# Shield_H-Bridge.net
KiCad netlist of a schematic drawn in EAGLE
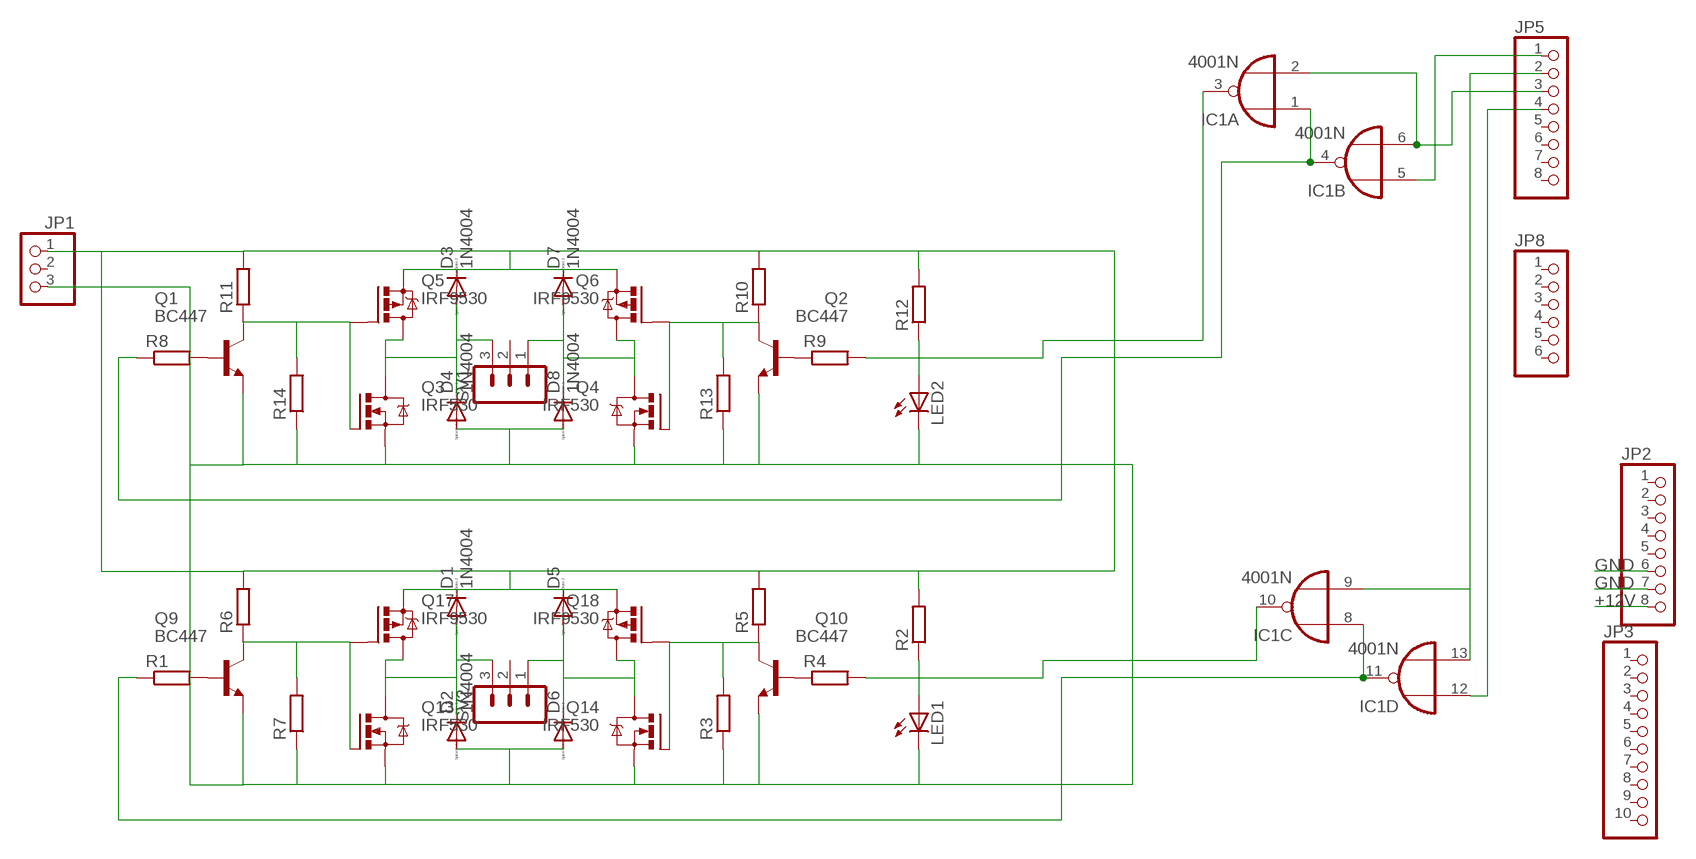
[diagram p0: schematic, sheet 1]

(export (version "E")
  (design (tool "Eeschema 10.0.6"))
  (components
    (comp (ref "D1")
      (value "1N4004")
      (footprint "eagle-import:DO41-10")
      (libsource (lib "eagle-import") (part "1N4004"))
    )
    (comp (ref "D2")
      (value "1N4004")
      (footprint "eagle-import:DO41-10")
      (libsource (lib "eagle-import") (part "1N4004"))
    )
    (comp (ref "D3")
      (value "1N4004")
      (footprint "eagle-import:DO41-10")
      (libsource (lib "eagle-import") (part "1N4004"))
    )
    (comp (ref "D4")
      (value "1N4004")
      (footprint "eagle-import:DO41-10")
      (libsource (lib "eagle-import") (part "1N4004"))
    )
    (comp (ref "D5")
      (value "1N4004")
      (footprint "eagle-import:DO41-10")
      (libsource (lib "eagle-import") (part "1N4004"))
    )
    (comp (ref "D6")
      (value "1N4004")
      (footprint "eagle-import:DO41-10")
      (libsource (lib "eagle-import") (part "1N4004"))
    )
    (comp (ref "D7")
      (value "1N4004")
      (footprint "eagle-import:DO41-10")
      (libsource (lib "eagle-import") (part "1N4004"))
    )
    (comp (ref "D8")
      (value "1N4004")
      (footprint "eagle-import:DO41-10")
      (libsource (lib "eagle-import") (part "1N4004"))
    )
    (comp (ref "IC1")
      (value "4001N")
      (footprint "eagle-import:DIL14")
      (libsource (lib "eagle-import") (part "4001N"))
    )
    (comp (ref "JP1")
      (value "PINHD-1X3")
      (footprint "eagle-import:1X03")
      (libsource (lib "eagle-import") (part "PINHD-1X3"))
    )
    (comp (ref "JP2")
      (value "PINHD-1X8")
      (footprint "eagle-import:1X08")
      (libsource (lib "eagle-import") (part "PINHD-1X8"))
    )
    (comp (ref "JP3")
      (value "PINHD-1X10")
      (footprint "eagle-import:1X10")
      (libsource (lib "eagle-import") (part "PINHD-1X10"))
    )
    (comp (ref "JP5")
      (value "PINHD-1X8")
      (footprint "eagle-import:1X08")
      (libsource (lib "eagle-import") (part "PINHD-1X8"))
    )
    (comp (ref "JP8")
      (value "PINHD-1X6")
      (footprint "eagle-import:1X06")
      (libsource (lib "eagle-import") (part "PINHD-1X6"))
    )
    (comp (ref "LED1")
      (value "LED3MM")
      (footprint "eagle-import:LED3MM")
      (libsource (lib "eagle-import") (part "LED3MM"))
    )
    (comp (ref "LED2")
      (value "LED3MM")
      (footprint "eagle-import:LED3MM")
      (libsource (lib "eagle-import") (part "LED3MM"))
    )
    (comp (ref "Q1")
      (value "BC447")
      (footprint "eagle-import:TO92-EBC")
      (libsource (lib "eagle-import") (part "BC447"))
    )
    (comp (ref "Q2")
      (value "BC447")
      (footprint "eagle-import:TO92-EBC")
      (libsource (lib "eagle-import") (part "BC447"))
    )
    (comp (ref "Q3")
      (value "IRF530")
      (footprint "eagle-import:TO220BV")
      (libsource (lib "eagle-import") (part "IRF530"))
    )
    (comp (ref "Q4")
      (value "IRF530")
      (footprint "eagle-import:TO220BV")
      (libsource (lib "eagle-import") (part "IRF530"))
    )
    (comp (ref "Q5")
      (value "IRF9530")
      (footprint "eagle-import:TO220BV")
      (libsource (lib "eagle-import") (part "IRF9530"))
    )
    (comp (ref "Q6")
      (value "IRF9530")
      (footprint "eagle-import:TO220BV")
      (libsource (lib "eagle-import") (part "IRF9530"))
    )
    (comp (ref "Q9")
      (value "BC447")
      (footprint "eagle-import:TO92-EBC")
      (libsource (lib "eagle-import") (part "BC447"))
    )
    (comp (ref "Q10")
      (value "BC447")
      (footprint "eagle-import:TO92-EBC")
      (libsource (lib "eagle-import") (part "BC447"))
    )
    (comp (ref "Q13")
      (value "IRF530")
      (footprint "eagle-import:TO220BV")
      (libsource (lib "eagle-import") (part "IRF530"))
    )
    (comp (ref "Q14")
      (value "IRF530")
      (footprint "eagle-import:TO220BV")
      (libsource (lib "eagle-import") (part "IRF530"))
    )
    (comp (ref "Q17")
      (value "IRF9530")
      (footprint "eagle-import:TO220BV")
      (libsource (lib "eagle-import") (part "IRF9530"))
    )
    (comp (ref "Q18")
      (value "IRF9530")
      (footprint "eagle-import:TO220BV")
      (libsource (lib "eagle-import") (part "IRF9530"))
    )
    (comp (ref "R1")
      (value "R-EU_0207/10")
      (footprint "eagle-import:0207_10")
      (libsource (lib "eagle-import") (part "R-EU_0207/10"))
    )
    (comp (ref "R2")
      (value "R-EU_0204/5")
      (footprint "eagle-import:0204_5")
      (libsource (lib "eagle-import") (part "R-EU_0204/5"))
    )
    (comp (ref "R3")
      (value "R-EU_0204/7")
      (footprint "eagle-import:0204_7")
      (libsource (lib "eagle-import") (part "R-EU_0204/7"))
    )
    (comp (ref "R4")
      (value "R-EU_0207/10")
      (footprint "eagle-import:0207_10")
      (libsource (lib "eagle-import") (part "R-EU_0207/10"))
    )
    (comp (ref "R5")
      (value "R-EU_0207/10")
      (footprint "eagle-import:0207_10")
      (libsource (lib "eagle-import") (part "R-EU_0207/10"))
    )
    (comp (ref "R6")
      (value "R-EU_0207/10")
      (footprint "eagle-import:0207_10")
      (libsource (lib "eagle-import") (part "R-EU_0207/10"))
    )
    (comp (ref "R7")
      (value "R-EU_0204/7")
      (footprint "eagle-import:0204_7")
      (libsource (lib "eagle-import") (part "R-EU_0204/7"))
    )
    (comp (ref "R8")
      (value "R-EU_0207/10")
      (footprint "eagle-import:0207_10")
      (libsource (lib "eagle-import") (part "R-EU_0207/10"))
    )
    (comp (ref "R9")
      (value "R-EU_0207/10")
      (footprint "eagle-import:0207_10")
      (libsource (lib "eagle-import") (part "R-EU_0207/10"))
    )
    (comp (ref "R10")
      (value "R-EU_0207/10")
      (footprint "eagle-import:0207_10")
      (libsource (lib "eagle-import") (part "R-EU_0207/10"))
    )
    (comp (ref "R11")
      (value "R-EU_0207/10")
      (footprint "eagle-import:0207_10")
      (libsource (lib "eagle-import") (part "R-EU_0207/10"))
    )
    (comp (ref "R12")
      (value "R-EU_0204/5")
      (footprint "eagle-import:0204_5")
      (libsource (lib "eagle-import") (part "R-EU_0204/5"))
    )
    (comp (ref "R13")
      (value "R-EU_0204/7")
      (footprint "eagle-import:0204_7")
      (libsource (lib "eagle-import") (part "R-EU_0204/7"))
    )
    (comp (ref "R14")
      (value "R-EU_0204/7")
      (footprint "eagle-import:0204_7")
      (libsource (lib "eagle-import") (part "R-EU_0204/7"))
    )
    (comp (ref "SV1")
      (value "MA03-1")
      (footprint "eagle-import:MA03-1")
      (libsource (lib "eagle-import") (part "MA03-1"))
    )
    (comp (ref "SV2")
      (value "MA03-1")
      (footprint "eagle-import:MA03-1")
      (libsource (lib "eagle-import") (part "MA03-1"))
    )
  )
  (nets
    (net (code "1") (name "/+12V") (class "Default")
      (node (ref "D1") (pin "C") (pinfunction "C_C") (pintype "passive"))
      (node (ref "D3") (pin "C") (pinfunction "C_C") (pintype "passive"))
      (node (ref "D5") (pin "C") (pinfunction "C_C") (pintype "passive"))
      (node (ref "D7") (pin "C") (pinfunction "C_C") (pintype "passive"))
      (node (ref "JP1") (pin "1") (pinfunction "1_1") (pintype "passive"))
      (node (ref "JP2") (pin "8") (pinfunction "8_8") (pintype "passive"))
      (node (ref "Q17") (pin "S") (pinfunction "S_S") (pintype "passive"))
      (node (ref "Q18") (pin "S") (pinfunction "S_S") (pintype "passive"))
      (node (ref "Q5") (pin "S") (pinfunction "S_S") (pintype "passive"))
      (node (ref "Q6") (pin "S") (pinfunction "S_S") (pintype "passive"))
      (node (ref "R10") (pin "2") (pinfunction "2_2") (pintype "passive"))
      (node (ref "R11") (pin "2") (pinfunction "2_2") (pintype "passive"))
      (node (ref "R12") (pin "2") (pinfunction "2_2") (pintype "passive"))
      (node (ref "R2") (pin "2") (pinfunction "2_2") (pintype "passive"))
      (node (ref "R5") (pin "2") (pinfunction "2_2") (pintype "passive"))
      (node (ref "R6") (pin "2") (pinfunction "2_2") (pintype "passive"))
    )
    (net (code "2") (name "/GND") (class "Default")
      (node (ref "D2") (pin "A") (pinfunction "A_A") (pintype "passive"))
      (node (ref "D4") (pin "A") (pinfunction "A_A") (pintype "passive"))
      (node (ref "D6") (pin "A") (pinfunction "A_A") (pintype "passive"))
      (node (ref "D8") (pin "A") (pinfunction "A_A") (pintype "passive"))
      (node (ref "JP1") (pin "3") (pinfunction "3_3") (pintype "passive"))
      (node (ref "JP2") (pin "6") (pinfunction "6_6") (pintype "passive"))
      (node (ref "JP2") (pin "7") (pinfunction "7_7") (pintype "passive"))
      (node (ref "LED1") (pin "K") (pinfunction "C_K") (pintype "passive"))
      (node (ref "LED2") (pin "K") (pinfunction "C_K") (pintype "passive"))
      (node (ref "Q1") (pin "E") (pinfunction "E_E") (pintype "passive"))
      (node (ref "Q10") (pin "E") (pinfunction "E_E") (pintype "passive"))
      (node (ref "Q13") (pin "S") (pinfunction "S_S") (pintype "passive"))
      (node (ref "Q14") (pin "S") (pinfunction "S_S") (pintype "passive"))
      (node (ref "Q2") (pin "E") (pinfunction "E_E") (pintype "passive"))
      (node (ref "Q3") (pin "S") (pinfunction "S_S") (pintype "passive"))
      (node (ref "Q4") (pin "S") (pinfunction "S_S") (pintype "passive"))
      (node (ref "Q9") (pin "E") (pinfunction "E_E") (pintype "passive"))
      (node (ref "R13") (pin "1") (pinfunction "1_1") (pintype "passive"))
      (node (ref "R14") (pin "1") (pinfunction "1_1") (pintype "passive"))
      (node (ref "R3") (pin "1") (pinfunction "1_1") (pintype "passive"))
      (node (ref "R7") (pin "1") (pinfunction "1_1") (pintype "passive"))
    )
    (net (code "3") (name "Net-(D1-PadA)") (class "Default")
      (node (ref "D1") (pin "A") (pinfunction "A_A") (pintype "passive"))
      (node (ref "D2") (pin "C") (pinfunction "C_C") (pintype "passive"))
      (node (ref "Q13") (pin "D") (pinfunction "D_D") (pintype "passive"))
      (node (ref "Q17") (pin "D") (pinfunction "D_D") (pintype "passive"))
      (node (ref "SV2") (pin "3") (pinfunction "3_3") (pintype "passive"))
    )
    (net (code "4") (name "Net-(D3-PadA)") (class "Default")
      (node (ref "D3") (pin "A") (pinfunction "A_A") (pintype "passive"))
      (node (ref "D4") (pin "C") (pinfunction "C_C") (pintype "passive"))
      (node (ref "Q3") (pin "D") (pinfunction "D_D") (pintype "passive"))
      (node (ref "Q5") (pin "D") (pinfunction "D_D") (pintype "passive"))
      (node (ref "SV1") (pin "3") (pinfunction "3_3") (pintype "passive"))
    )
    (net (code "5") (name "Net-(D5-PadA)") (class "Default")
      (node (ref "D5") (pin "A") (pinfunction "A_A") (pintype "passive"))
      (node (ref "D6") (pin "C") (pinfunction "C_C") (pintype "passive"))
      (node (ref "Q14") (pin "D") (pinfunction "D_D") (pintype "passive"))
      (node (ref "Q18") (pin "D") (pinfunction "D_D") (pintype "passive"))
      (node (ref "SV2") (pin "1") (pinfunction "1_1") (pintype "passive"))
    )
    (net (code "6") (name "Net-(D7-PadA)") (class "Default")
      (node (ref "D7") (pin "A") (pinfunction "A_A") (pintype "passive"))
      (node (ref "D8") (pin "C") (pinfunction "C_C") (pintype "passive"))
      (node (ref "Q4") (pin "D") (pinfunction "D_D") (pintype "passive"))
      (node (ref "Q6") (pin "D") (pinfunction "D_D") (pintype "passive"))
      (node (ref "SV1") (pin "1") (pinfunction "1_1") (pintype "passive"))
    )
    (net (code "7") (name "Net-(IC1A-I0)") (class "Default")
      (node (ref "IC1") (pin "1") (pinfunction "I0_1") (pintype "input"))
      (node (ref "IC1") (pin "4") (pinfunction "O_4") (pintype "output"))
      (node (ref "R8") (pin "1") (pinfunction "1_1") (pintype "passive"))
    )
    (net (code "8") (name "Net-(IC1A-I1)") (class "Default")
      (node (ref "IC1") (pin "2") (pinfunction "I1_2") (pintype "input"))
      (node (ref "IC1") (pin "6") (pinfunction "I1_6") (pintype "input"))
      (node (ref "JP5") (pin "3") (pinfunction "3_3") (pintype "passive"))
    )
    (net (code "9") (name "Net-(IC1A-O)") (class "Default")
      (node (ref "IC1") (pin "3") (pinfunction "O_3") (pintype "output"))
      (node (ref "R9") (pin "2") (pinfunction "2_2") (pintype "passive"))
    )
    (net (code "10") (name "Net-(IC1B-I0)") (class "Default")
      (node (ref "IC1") (pin "5") (pinfunction "I0_5") (pintype "input"))
      (node (ref "JP5") (pin "1") (pinfunction "1_1") (pintype "passive"))
    )
    (net (code "11") (name "Net-(IC1C-I0)") (class "Default")
      (node (ref "IC1") (pin "11") (pinfunction "O_11") (pintype "output"))
      (node (ref "IC1") (pin "8") (pinfunction "I0_8") (pintype "input"))
      (node (ref "R1") (pin "1") (pinfunction "1_1") (pintype "passive"))
    )
    (net (code "12") (name "Net-(IC1C-I1)") (class "Default")
      (node (ref "IC1") (pin "13") (pinfunction "I1_13") (pintype "input"))
      (node (ref "IC1") (pin "9") (pinfunction "I1_9") (pintype "input"))
      (node (ref "JP5") (pin "2") (pinfunction "2_2") (pintype "passive"))
    )
    (net (code "13") (name "Net-(IC1C-O)") (class "Default")
      (node (ref "IC1") (pin "10") (pinfunction "O_10") (pintype "output"))
      (node (ref "R4") (pin "2") (pinfunction "2_2") (pintype "passive"))
    )
    (net (code "14") (name "Net-(IC1D-I0)") (class "Default")
      (node (ref "IC1") (pin "12") (pinfunction "I0_12") (pintype "input"))
      (node (ref "JP5") (pin "4") (pinfunction "4_4") (pintype "passive"))
    )
    (net (code "15") (name "Net-(LED1-PadA)") (class "Default")
      (node (ref "LED1") (pin "A") (pinfunction "A_A") (pintype "passive"))
      (node (ref "R2") (pin "1") (pinfunction "1_1") (pintype "passive"))
    )
    (net (code "16") (name "Net-(LED2-PadA)") (class "Default")
      (node (ref "LED2") (pin "A") (pinfunction "A_A") (pintype "passive"))
      (node (ref "R12") (pin "1") (pinfunction "1_1") (pintype "passive"))
    )
    (net (code "17") (name "Net-(Q1-PadB)") (class "Default")
      (node (ref "Q1") (pin "B") (pinfunction "B_B") (pintype "passive"))
      (node (ref "R8") (pin "2") (pinfunction "2_2") (pintype "passive"))
    )
    (net (code "18") (name "Net-(Q1-PadC)") (class "Default")
      (node (ref "Q1") (pin "C") (pinfunction "C_C") (pintype "passive"))
      (node (ref "Q3") (pin "G") (pinfunction "G_G") (pintype "passive"))
      (node (ref "Q5") (pin "G") (pinfunction "G_G") (pintype "passive"))
      (node (ref "R11") (pin "1") (pinfunction "1_1") (pintype "passive"))
      (node (ref "R14") (pin "2") (pinfunction "2_2") (pintype "passive"))
    )
    (net (code "19") (name "Net-(Q2-PadB)") (class "Default")
      (node (ref "Q2") (pin "B") (pinfunction "B_B") (pintype "passive"))
      (node (ref "R9") (pin "1") (pinfunction "1_1") (pintype "passive"))
    )
    (net (code "20") (name "Net-(Q2-PadC)") (class "Default")
      (node (ref "Q2") (pin "C") (pinfunction "C_C") (pintype "passive"))
      (node (ref "Q4") (pin "G") (pinfunction "G_G") (pintype "passive"))
      (node (ref "Q6") (pin "G") (pinfunction "G_G") (pintype "passive"))
      (node (ref "R10") (pin "1") (pinfunction "1_1") (pintype "passive"))
      (node (ref "R13") (pin "2") (pinfunction "2_2") (pintype "passive"))
    )
    (net (code "21") (name "Net-(Q9-PadB)") (class "Default")
      (node (ref "Q9") (pin "B") (pinfunction "B_B") (pintype "passive"))
      (node (ref "R1") (pin "2") (pinfunction "2_2") (pintype "passive"))
    )
    (net (code "22") (name "Net-(Q10-PadB)") (class "Default")
      (node (ref "Q10") (pin "B") (pinfunction "B_B") (pintype "passive"))
      (node (ref "R4") (pin "1") (pinfunction "1_1") (pintype "passive"))
    )
    (net (code "23") (name "Net-(Q10-PadC)") (class "Default")
      (node (ref "Q10") (pin "C") (pinfunction "C_C") (pintype "passive"))
      (node (ref "Q14") (pin "G") (pinfunction "G_G") (pintype "passive"))
      (node (ref "Q18") (pin "G") (pinfunction "G_G") (pintype "passive"))
      (node (ref "R3") (pin "2") (pinfunction "2_2") (pintype "passive"))
      (node (ref "R5") (pin "1") (pinfunction "1_1") (pintype "passive"))
    )
    (net (code "24") (name "Net-(Q13-PadG)") (class "Default")
      (node (ref "Q13") (pin "G") (pinfunction "G_G") (pintype "passive"))
      (node (ref "Q17") (pin "G") (pinfunction "G_G") (pintype "passive"))
      (node (ref "Q9") (pin "C") (pinfunction "C_C") (pintype "passive"))
      (node (ref "R6") (pin "1") (pinfunction "1_1") (pintype "passive"))
      (node (ref "R7") (pin "2") (pinfunction "2_2") (pintype "passive"))
    )
    (net (code "25") (name "unconnected-(JP1-Pad2)") (class "Default")
      (node (ref "JP1") (pin "2") (pinfunction "2_2") (pintype "passive"))
    )
    (net (code "26") (name "unconnected-(JP2-Pad1)") (class "Default")
      (node (ref "JP2") (pin "1") (pinfunction "1_1") (pintype "passive"))
    )
    (net (code "27") (name "unconnected-(JP2-Pad2)") (class "Default")
      (node (ref "JP2") (pin "2") (pinfunction "2_2") (pintype "passive"))
    )
    (net (code "28") (name "unconnected-(JP2-Pad3)") (class "Default")
      (node (ref "JP2") (pin "3") (pinfunction "3_3") (pintype "passive"))
    )
    (net (code "29") (name "unconnected-(JP2-Pad4)") (class "Default")
      (node (ref "JP2") (pin "4") (pinfunction "4_4") (pintype "passive"))
    )
    (net (code "30") (name "unconnected-(JP2-Pad5)") (class "Default")
      (node (ref "JP2") (pin "5") (pinfunction "5_5") (pintype "passive"))
    )
    (net (code "31") (name "unconnected-(JP3-Pad1)") (class "Default")
      (node (ref "JP3") (pin "1") (pinfunction "1_1") (pintype "passive"))
    )
    (net (code "32") (name "unconnected-(JP3-Pad2)") (class "Default")
      (node (ref "JP3") (pin "2") (pinfunction "2_2") (pintype "passive"))
    )
    (net (code "33") (name "unconnected-(JP3-Pad3)") (class "Default")
      (node (ref "JP3") (pin "3") (pinfunction "3_3") (pintype "passive"))
    )
    (net (code "34") (name "unconnected-(JP3-Pad4)") (class "Default")
      (node (ref "JP3") (pin "4") (pinfunction "4_4") (pintype "passive"))
    )
    (net (code "35") (name "unconnected-(JP3-Pad5)") (class "Default")
      (node (ref "JP3") (pin "5") (pinfunction "5_5") (pintype "passive"))
    )
    (net (code "36") (name "unconnected-(JP3-Pad6)") (class "Default")
      (node (ref "JP3") (pin "6") (pinfunction "6_6") (pintype "passive"))
    )
    (net (code "37") (name "unconnected-(JP3-Pad7)") (class "Default")
      (node (ref "JP3") (pin "7") (pinfunction "7_7") (pintype "passive"))
    )
    (net (code "38") (name "unconnected-(JP3-Pad8)") (class "Default")
      (node (ref "JP3") (pin "8") (pinfunction "8_8") (pintype "passive"))
    )
    (net (code "39") (name "unconnected-(JP3-Pad9)") (class "Default")
      (node (ref "JP3") (pin "9") (pinfunction "9_9") (pintype "passive"))
    )
    (net (code "40") (name "unconnected-(JP3-Pad10)") (class "Default")
      (node (ref "JP3") (pin "10") (pinfunction "10_10") (pintype "passive"))
    )
    (net (code "41") (name "unconnected-(JP5-Pad5)") (class "Default")
      (node (ref "JP5") (pin "5") (pinfunction "5_5") (pintype "passive"))
    )
    (net (code "42") (name "unconnected-(JP5-Pad6)") (class "Default")
      (node (ref "JP5") (pin "6") (pinfunction "6_6") (pintype "passive"))
    )
    (net (code "43") (name "unconnected-(JP5-Pad7)") (class "Default")
      (node (ref "JP5") (pin "7") (pinfunction "7_7") (pintype "passive"))
    )
    (net (code "44") (name "unconnected-(JP5-Pad8)") (class "Default")
      (node (ref "JP5") (pin "8") (pinfunction "8_8") (pintype "passive"))
    )
    (net (code "45") (name "unconnected-(JP8-Pad1)") (class "Default")
      (node (ref "JP8") (pin "1") (pinfunction "1_1") (pintype "passive"))
    )
    (net (code "46") (name "unconnected-(JP8-Pad2)") (class "Default")
      (node (ref "JP8") (pin "2") (pinfunction "2_2") (pintype "passive"))
    )
    (net (code "47") (name "unconnected-(JP8-Pad3)") (class "Default")
      (node (ref "JP8") (pin "3") (pinfunction "3_3") (pintype "passive"))
    )
    (net (code "48") (name "unconnected-(JP8-Pad4)") (class "Default")
      (node (ref "JP8") (pin "4") (pinfunction "4_4") (pintype "passive"))
    )
    (net (code "49") (name "unconnected-(JP8-Pad5)") (class "Default")
      (node (ref "JP8") (pin "5") (pinfunction "5_5") (pintype "passive"))
    )
    (net (code "50") (name "unconnected-(JP8-Pad6)") (class "Default")
      (node (ref "JP8") (pin "6") (pinfunction "6_6") (pintype "passive"))
    )
    (net (code "51") (name "unconnected-(SV1-Pad2)") (class "Default")
      (node (ref "SV1") (pin "2") (pinfunction "2_2") (pintype "passive"))
    )
    (net (code "52") (name "unconnected-(SV2-Pad2)") (class "Default")
      (node (ref "SV2") (pin "2") (pinfunction "2_2") (pintype "passive"))
    )
  )
)
